# Isolated-Inputs-Schematic.net
KiCad netlist of a schematic drawn in Altium Designer
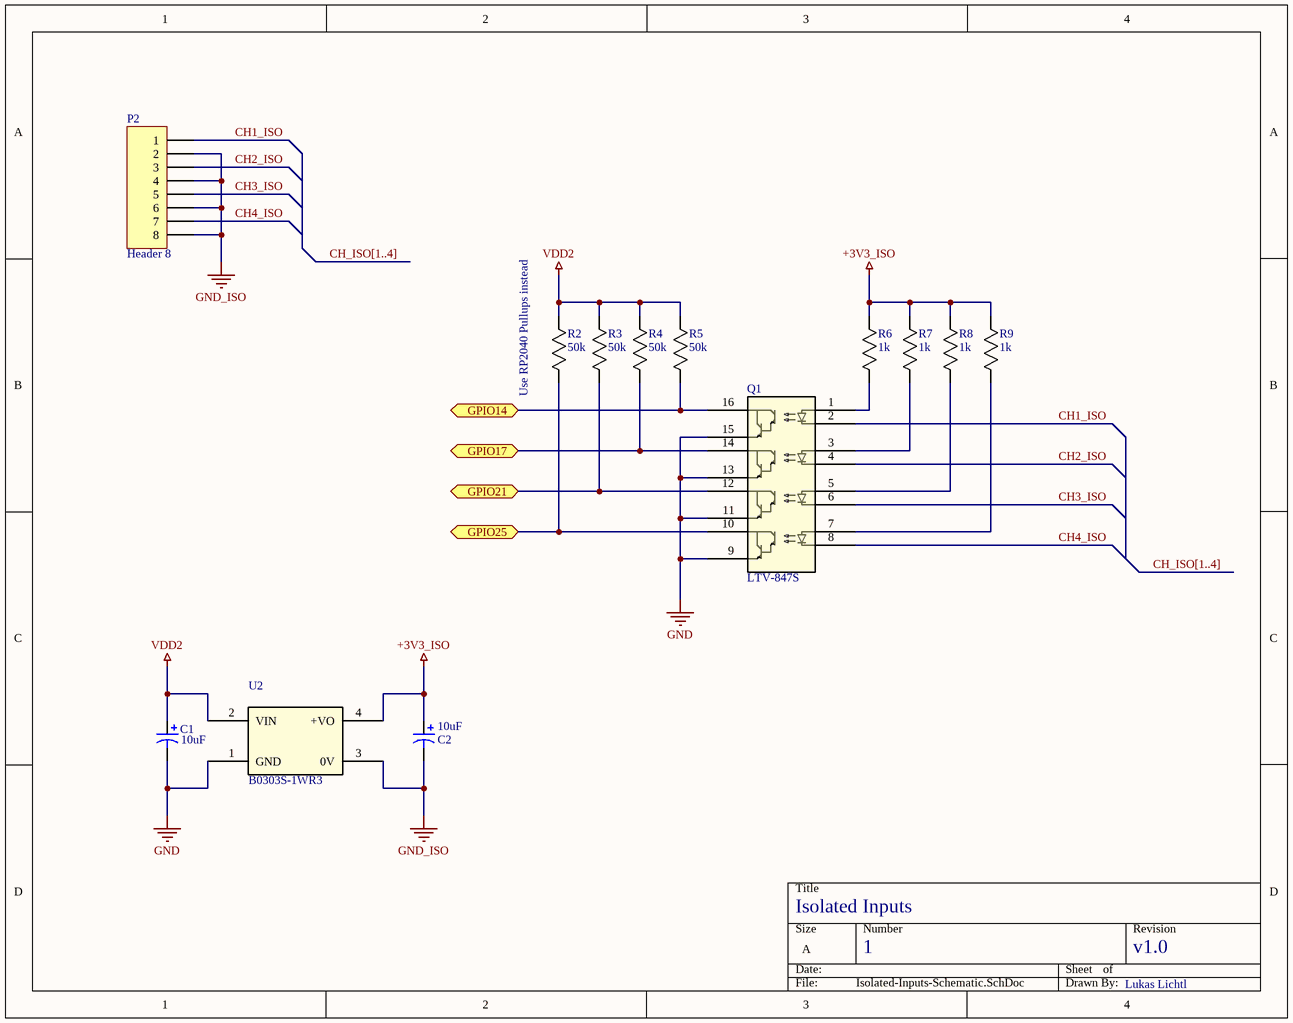
[diagram p0: Isolated-Inputs-Schematic.SchDoc]

(export (version "E")
  (design (tool "Eeschema 10.0.6"))
  (components
    (comp (ref "C1")
      (value "10uF")
      (footprint "C0805")
      (description "Polarized Capacitor (Surface Mount)")
      (fields (field (name "Comment") "Cap Pol3") (field (name "PUBLISHER") "Altium Limited"))
      (libsource (lib "Miscellaneous Devices") (part "Cap Pol3"))
    )
    (comp (ref "C2")
      (value "10uF")
      (footprint "C0805")
      (description "Polarized Capacitor (Surface Mount)")
      (fields (field (name "Comment") "Cap Pol3") (field (name "PUBLISHER") "Altium Limited"))
      (libsource (lib "Miscellaneous Devices") (part "Cap Pol3"))
    )
    (comp (ref "P2")
      (value "Header 8")
      (footprint "HDR1X8")
      (description "Header, 8-Pin")
      (fields (field (name "PUBLISHER") "Altium Limited"))
      (libsource (lib "Miscellaneous Connectors") (part "Header 8"))
    )
    (comp (ref "Q1")
      (value "LTV-847S")
      (footprint "LTV-847S_LTO")
      (description "No Description Available")
      (libsource (lib "LTV-847S") (part "LTV-847S"))
    )
    (comp (ref "R2")
      (value "50k")
      (footprint "RC0603N_YAG")
      (description "No Description Available")
      (libsource (lib "RC0603FR-07470RL") (part "RC0603FR-07470RL"))
    )
    (comp (ref "R3")
      (value "50k")
      (footprint "RC0603N_YAG")
      (description "No Description Available")
      (libsource (lib "RC0603FR-07470RL") (part "RC0603FR-07470RL"))
    )
    (comp (ref "R4")
      (value "50k")
      (footprint "RC0603N_YAG")
      (description "No Description Available")
      (libsource (lib "RC0603FR-07470RL") (part "RC0603FR-07470RL"))
    )
    (comp (ref "R5")
      (value "50k")
      (footprint "RC0603N_YAG")
      (libsource (lib "RC0603FR-07470RL") (part "RC0603FR-07470RL"))
    )
    (comp (ref "R6")
      (value "1k")
      (footprint "RC0603N_YAG")
      (description "No Description Available")
      (libsource (lib "RC0603FR-07470RL") (part "RC0603FR-07470RL"))
    )
    (comp (ref "R7")
      (value "1k")
      (footprint "RC0603N_YAG")
      (description "No Description Available")
      (libsource (lib "RC0603FR-07470RL") (part "RC0603FR-07470RL"))
    )
    (comp (ref "R8")
      (value "1k")
      (footprint "RC0603N_YAG")
      (description "No Description Available")
      (libsource (lib "RC0603FR-07470RL") (part "RC0603FR-07470RL"))
    )
    (comp (ref "R9")
      (value "1k")
      (footprint "RC0603N_YAG")
      (description "No Description Available")
      (libsource (lib "RC0603FR-07470RL") (part "RC0603FR-07470RL"))
    )
    (comp (ref "U2")
      (value "B0303S-1WR3")
      (footprint "SIP4_B_S-1WR3_MNS")
      (libsource (lib "B0303S-1WR3") (part "B0303S-1WR3"))
    )
  )
  (nets
    (net (code "5") (name "+3V3_ISO") (class "Default")
      (node (ref "C2") (pin "1") (pinfunction "1_1") (pintype "passive"))
      (node (ref "R6") (pin "2") (pinfunction "2_2") (pintype "passive"))
      (node (ref "R7") (pin "2") (pinfunction "2_2") (pintype "passive"))
      (node (ref "R8") (pin "2") (pinfunction "2_2") (pintype "passive"))
      (node (ref "R9") (pin "2") (pinfunction "2_2") (pintype "passive"))
      (node (ref "U2") (pin "4") (pinfunction "+VO_4") (pintype "power_in"))
    )
    (net (code "6") (name "/CH1_ISO") (class "Default")
      (node (ref "P2") (pin "1") (pinfunction "1_1") (pintype "passive"))
      (node (ref "Q1") (pin "2") (pinfunction "2_2") (pintype "passive"))
    )
    (net (code "7") (name "/CH2_ISO") (class "Default")
      (node (ref "P2") (pin "3") (pinfunction "3_3") (pintype "passive"))
      (node (ref "Q1") (pin "4") (pinfunction "4_4") (pintype "passive"))
    )
    (net (code "8") (name "/CH3_ISO") (class "Default")
      (node (ref "P2") (pin "5") (pinfunction "5_5") (pintype "passive"))
      (node (ref "Q1") (pin "6") (pinfunction "6_6") (pintype "passive"))
    )
    (net (code "9") (name "/CH4_ISO") (class "Default")
      (node (ref "P2") (pin "7") (pinfunction "7_7") (pintype "passive"))
      (node (ref "Q1") (pin "8") (pinfunction "8_8") (pintype "passive"))
    )
    (net (code "11") (name "/GPIO14") (class "Default")
      (node (ref "Q1") (pin "16") (pinfunction "16_16") (pintype "passive"))
      (node (ref "R5") (pin "1") (pinfunction "1_1") (pintype "passive"))
    )
    (net (code "12") (name "/GPIO17") (class "Default")
      (node (ref "Q1") (pin "14") (pinfunction "14_14") (pintype "passive"))
      (node (ref "R4") (pin "1") (pinfunction "1_1") (pintype "passive"))
    )
    (net (code "13") (name "/GPIO21") (class "Default")
      (node (ref "Q1") (pin "12") (pinfunction "12_12") (pintype "passive"))
      (node (ref "R3") (pin "1") (pinfunction "1_1") (pintype "passive"))
    )
    (net (code "14") (name "/GPIO25") (class "Default")
      (node (ref "Q1") (pin "10") (pinfunction "10_10") (pintype "passive"))
      (node (ref "R2") (pin "1") (pinfunction "1_1") (pintype "passive"))
    )
    (net (code "15") (name "GND") (class "Default")
      (node (ref "C1") (pin "2") (pinfunction "2_2") (pintype "passive"))
      (node (ref "Q1") (pin "11") (pinfunction "11_11") (pintype "passive"))
      (node (ref "Q1") (pin "13") (pinfunction "13_13") (pintype "passive"))
      (node (ref "Q1") (pin "15") (pinfunction "15_15") (pintype "passive"))
      (node (ref "Q1") (pin "9") (pinfunction "9_9") (pintype "passive"))
      (node (ref "U2") (pin "1") (pinfunction "GND_1") (pintype "power_in"))
    )
    (net (code "16") (name "GND_ISO") (class "Default")
      (node (ref "C2") (pin "2") (pinfunction "2_2") (pintype "passive"))
      (node (ref "P2") (pin "2") (pinfunction "2_2") (pintype "passive"))
      (node (ref "P2") (pin "4") (pinfunction "4_4") (pintype "passive"))
      (node (ref "P2") (pin "6") (pinfunction "6_6") (pintype "passive"))
      (node (ref "P2") (pin "8") (pinfunction "8_8") (pintype "passive"))
      (node (ref "U2") (pin "3") (pinfunction "0V_3") (pintype "passive"))
    )
    (net (code "17") (name "Net-(Q1-Pad1)") (class "Default")
      (node (ref "Q1") (pin "1") (pinfunction "1_1") (pintype "passive"))
      (node (ref "R6") (pin "1") (pinfunction "1_1") (pintype "passive"))
    )
    (net (code "18") (name "Net-(Q1-Pad3)") (class "Default")
      (node (ref "Q1") (pin "3") (pinfunction "3_3") (pintype "passive"))
      (node (ref "R7") (pin "1") (pinfunction "1_1") (pintype "passive"))
    )
    (net (code "19") (name "Net-(Q1-Pad5)") (class "Default")
      (node (ref "Q1") (pin "5") (pinfunction "5_5") (pintype "passive"))
      (node (ref "R8") (pin "1") (pinfunction "1_1") (pintype "passive"))
    )
    (net (code "20") (name "Net-(Q1-Pad7)") (class "Default")
      (node (ref "Q1") (pin "7") (pinfunction "7_7") (pintype "passive"))
      (node (ref "R9") (pin "1") (pinfunction "1_1") (pintype "passive"))
    )
    (net (code "21") (name "VDD2") (class "Default")
      (node (ref "C1") (pin "1") (pinfunction "1_1") (pintype "passive"))
      (node (ref "R2") (pin "2") (pinfunction "2_2") (pintype "passive"))
      (node (ref "R3") (pin "2") (pinfunction "2_2") (pintype "passive"))
      (node (ref "R4") (pin "2") (pinfunction "2_2") (pintype "passive"))
      (node (ref "R5") (pin "2") (pinfunction "2_2") (pintype "passive"))
      (node (ref "U2") (pin "2") (pinfunction "VIN_2") (pintype "power_in"))
    )
  )
)
